# Photodiode.net
KiCad netlist of a schematic drawn in Altium Designer
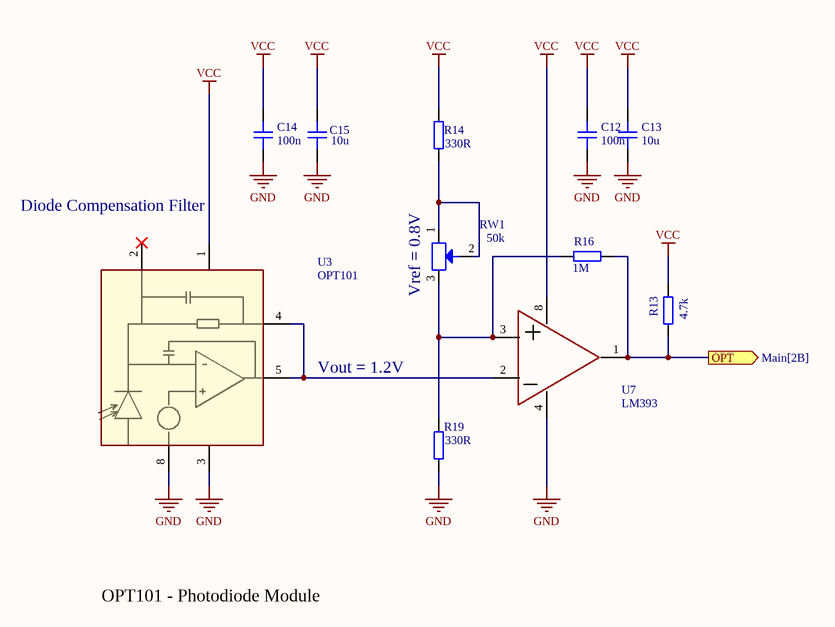
[diagram p0: Photodiode.SchDoc]

(export (version "E")
  (design (tool "Eeschema 10.0.6"))
  (components
    (comp (ref "C12")
      (value "100n")
      (footprint "CAP_0805")
      (description "Capacitor SMD 0805")
      (libsource (lib "Schematic-Lib-PhilsLab") (part "CAP_0805"))
    )
    (comp (ref "C13")
      (value "10u")
      (footprint "CAP_0805")
      (description "Capacitor SMD 0805")
      (libsource (lib "Schematic-Lib-PhilsLab") (part "CAP_0805"))
    )
    (comp (ref "C14")
      (value "100n")
      (footprint "CAP_0805")
      (description "Capacitor SMD 0805")
      (libsource (lib "Schematic-Lib-PhilsLab") (part "CAP_0805"))
    )
    (comp (ref "C15")
      (value "10u")
      (footprint "CAP_0805")
      (description "Capacitor SMD 0805")
      (libsource (lib "Schematic-Lib-PhilsLab") (part "CAP_0805"))
    )
    (comp (ref "R13")
      (value "4.7k")
      (footprint "RES_0805")
      (description "Resistor SMD 0805")
      (libsource (lib "Schematic-Lib-PhilsLab") (part "RES_0805"))
    )
    (comp (ref "R14")
      (value "330R")
      (footprint "RES_0805")
      (description "Resistor SMD 0805")
      (libsource (lib "Schematic-Lib-PhilsLab") (part "RES_0805"))
    )
    (comp (ref "R16")
      (value "1M")
      (footprint "RES_0805")
      (description "Resistor SMD 0805")
      (libsource (lib "Schematic-Lib-PhilsLab") (part "RES_0805"))
    )
    (comp (ref "R19")
      (value "330R")
      (footprint "RES_0805")
      (description "Resistor SMD 0805")
      (libsource (lib "Schematic-Lib-PhilsLab") (part "RES_0805"))
    )
    (comp (ref "RW1")
      (value "50k")
      (footprint "Potentiometer")
      (libsource (lib "Schematic_Library_TM") (part "Potentiometer"))
    )
    (comp (ref "U3")
      (value "OPT101")
      (footprint "PCB_Library_TM:OPT101")
      (description "Photodiode Module")
      (libsource (lib "Schematic_Library_TM") (part "OPT101"))
    )
    (comp (ref "U7")
      (value "LM393")
      (footprint "LM393")
      (description "LLM393 - Comparator")
      (libsource (lib "Schematic_Library_TM") (part "LM393"))
    )
  )
  (nets
    (net (code "1") (name "/OPT") (class "Default")
      (node (ref "R13") (pin "1") (pinfunction "1_1") (pintype "passive"))
      (node (ref "R16") (pin "1") (pinfunction "1_1") (pintype "passive"))
      (node (ref "U7") (pin "1") (pinfunction "OUT_1") (pintype "passive"))
    )
    (net (code "2") (name "GND") (class "Default")
      (node (ref "C12") (pin "1") (pinfunction "1_1") (pintype "passive"))
      (node (ref "C13") (pin "1") (pinfunction "1_1") (pintype "passive"))
      (node (ref "C14") (pin "1") (pinfunction "1_1") (pintype "passive"))
      (node (ref "C15") (pin "1") (pinfunction "1_1") (pintype "passive"))
      (node (ref "R19") (pin "1") (pinfunction "1_1") (pintype "passive"))
      (node (ref "U3") (pin "3") (pinfunction "17_3") (pintype "passive"))
      (node (ref "U3") (pin "8") (pinfunction "17_8") (pintype "passive"))
      (node (ref "U7") (pin "4") (pinfunction "VSS_4") (pintype "passive"))
    )
    (net (code "3") (name "Net-(RW1-4)") (class "Default")
      (node (ref "R14") (pin "1") (pinfunction "1_1") (pintype "passive"))
      (node (ref "RW1") (pin "1") (pinfunction "4_1") (pintype "power_in"))
      (node (ref "RW1") (pin "2") (pinfunction "5_2") (pintype "power_in"))
    )
    (net (code "4") (name "Net-(RW1-6)") (class "Default")
      (node (ref "R16") (pin "2") (pinfunction "2_2") (pintype "passive"))
      (node (ref "R19") (pin "2") (pinfunction "2_2") (pintype "passive"))
      (node (ref "RW1") (pin "3") (pinfunction "6_3") (pintype "power_in"))
      (node (ref "U7") (pin "3") (pinfunction "3_3") (pintype "passive"))
    )
    (net (code "5") (name "Net-(U7-14)") (class "Default")
      (node (ref "U3") (pin "4") (pinfunction "17_4") (pintype "passive"))
      (node (ref "U3") (pin "5") (pinfunction "17_5") (pintype "passive"))
      (node (ref "U7") (pin "2") (pinfunction "14_2") (pintype "passive"))
    )
    (net (code "6") (name "VCC") (class "Default")
      (node (ref "C12") (pin "2") (pinfunction "2_2") (pintype "passive"))
      (node (ref "C13") (pin "2") (pinfunction "2_2") (pintype "passive"))
      (node (ref "C14") (pin "2") (pinfunction "2_2") (pintype "passive"))
      (node (ref "C15") (pin "2") (pinfunction "2_2") (pintype "passive"))
      (node (ref "R13") (pin "2") (pinfunction "2_2") (pintype "passive"))
      (node (ref "R14") (pin "2") (pinfunction "2_2") (pintype "passive"))
      (node (ref "U3") (pin "1") (pinfunction "17_1") (pintype "passive"))
      (node (ref "U7") (pin "8") (pinfunction "16_8") (pintype "passive"))
    )
    (net (code "7") (name "unconnected-(U3-17-Pad2)") (class "Default")
      (node (ref "U3") (pin "2") (pinfunction "17_2") (pintype "passive+no_connect"))
    )
  )
)
